# RelayExtension.net
KiCad netlist of a schematic drawn in Altium Designer
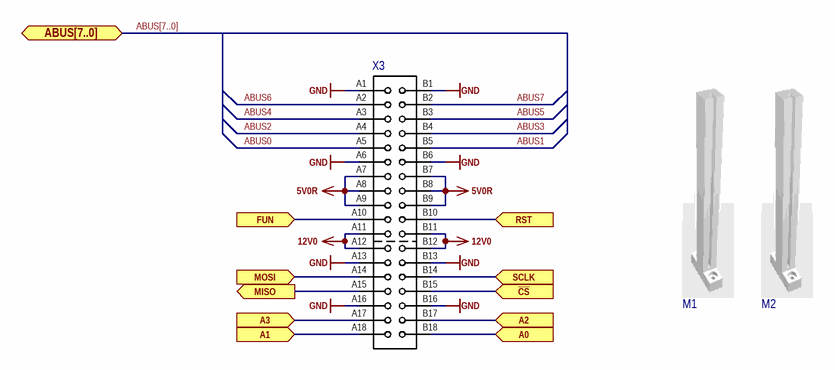
[diagram p0: RelayExtension.SchDoc]

(export (version "E")
  (design (tool "Eeschema 10.0.6"))
  (components
    (comp (ref "M1")
      (value "PCB Support")
      (footprint "PCB Tester Support")
      (fields
        (field (name "07. MANUFACTURER  PART NUMBER") "TBD")
        (field (name "13. CREATED DATE/NAME") "??? / Hören")
      )
      (libsource (lib "PCB-Tester-Board-V1") (part "PCB Tester Support"))
    )
    (comp (ref "M2")
      (value "PCB Support")
      (footprint "PCB Tester Support")
      (fields
        (field (name "07. MANUFACTURER  PART NUMBER") "TBD")
        (field (name "13. CREATED DATE/NAME") "??? / Hören")
      )
      (libsource (lib "PCB-Tester-Board-V1") (part "PCB Tester Support"))
    )
    (comp (ref "X3")
      (value "X")
      (footprint "PCIE-036-02-F-D-TH")
      (description "CONN PCI EXP FMALE 36POS 0.039")
      (fields
        (field (name "02. DISTRIBUTOR PART NUMBER") "SAM10625-ND")
        (field (name "07. MANUFACTURER  PART NUMBER") "PCIE-036-02-F-D-TH")
        (field (name "13. CREATED DATE/NAME") "??? / Hören")
      )
      (libsource (lib "Connectors") (part "PCIE-036-02-F-D-TH"))
    )
  )
  (nets
    (net (code "1") (name "/A0") (class "Default")
      (node (ref "X3") (pin "B18") (pinfunction "B18_B18") (pintype "passive"))
    )
    (net (code "2") (name "/A1") (class "Default")
      (node (ref "X3") (pin "A18") (pinfunction "A18_A18") (pintype "passive"))
    )
    (net (code "3") (name "/A2") (class "Default")
      (node (ref "X3") (pin "B17") (pinfunction "B17_B17") (pintype "passive"))
    )
    (net (code "4") (name "/A3") (class "Default")
      (node (ref "X3") (pin "A17") (pinfunction "A17_A17") (pintype "passive"))
    )
    (net (code "5") (name "/ABUS0") (class "Default")
      (node (ref "X3") (pin "A5") (pinfunction "A5_A5") (pintype "passive"))
    )
    (net (code "6") (name "/ABUS1") (class "Default")
      (node (ref "X3") (pin "B5") (pinfunction "B5_B5") (pintype "passive"))
    )
    (net (code "7") (name "/ABUS2") (class "Default")
      (node (ref "X3") (pin "A4") (pinfunction "A4_A4") (pintype "passive"))
    )
    (net (code "8") (name "/ABUS3") (class "Default")
      (node (ref "X3") (pin "B4") (pinfunction "B4_B4") (pintype "passive"))
    )
    (net (code "9") (name "/ABUS4") (class "Default")
      (node (ref "X3") (pin "A3") (pinfunction "A3_A3") (pintype "passive"))
    )
    (net (code "10") (name "/ABUS5") (class "Default")
      (node (ref "X3") (pin "B3") (pinfunction "B3_B3") (pintype "passive"))
    )
    (net (code "11") (name "/ABUS6") (class "Default")
      (node (ref "X3") (pin "A2") (pinfunction "A2_A2") (pintype "passive"))
    )
    (net (code "12") (name "/ABUS7") (class "Default")
      (node (ref "X3") (pin "B2") (pinfunction "B2_B2") (pintype "passive"))
    )
    (net (code "14") (name "/CS") (class "Default")
      (node (ref "X3") (pin "B15") (pinfunction "B15_B15") (pintype "passive"))
    )
    (net (code "15") (name "/FUN") (class "Default")
      (node (ref "X3") (pin "A10") (pinfunction "A10_A10") (pintype "passive"))
    )
    (net (code "16") (name "/MISO") (class "Default")
      (node (ref "X3") (pin "A15") (pinfunction "A15_A15") (pintype "passive"))
    )
    (net (code "17") (name "/MOSI") (class "Default")
      (node (ref "X3") (pin "A14") (pinfunction "A14_A14") (pintype "passive"))
    )
    (net (code "18") (name "/RST") (class "Default")
      (node (ref "X3") (pin "B10") (pinfunction "B10_B10") (pintype "passive"))
    )
    (net (code "19") (name "/SCLK") (class "Default")
      (node (ref "X3") (pin "B14") (pinfunction "B14_B14") (pintype "passive"))
    )
    (net (code "20") (name "5V0R") (class "Default")
      (node (ref "X3") (pin "A7") (pinfunction "A7_A7") (pintype "passive"))
      (node (ref "X3") (pin "A8") (pinfunction "A8_A8") (pintype "passive"))
      (node (ref "X3") (pin "A9") (pinfunction "A9_A9") (pintype "passive"))
      (node (ref "X3") (pin "B7") (pinfunction "B7_B7") (pintype "passive"))
      (node (ref "X3") (pin "B8") (pinfunction "B8_B8") (pintype "passive"))
      (node (ref "X3") (pin "B9") (pinfunction "B9_B9") (pintype "passive"))
    )
    (net (code "21") (name "12V0") (class "Default")
      (node (ref "X3") (pin "A11") (pinfunction "A11_A11") (pintype "passive"))
      (node (ref "X3") (pin "A12") (pinfunction "A12_A12") (pintype "passive"))
      (node (ref "X3") (pin "B11") (pinfunction "B11_B11") (pintype "passive"))
      (node (ref "X3") (pin "B12") (pinfunction "B12_B12") (pintype "passive"))
    )
    (net (code "22") (name "GND") (class "Default")
      (node (ref "X3") (pin "A1") (pinfunction "A1_A1") (pintype "passive"))
      (node (ref "X3") (pin "A13") (pinfunction "A13_A13") (pintype "passive"))
      (node (ref "X3") (pin "A16") (pinfunction "A16_A16") (pintype "passive"))
      (node (ref "X3") (pin "A6") (pinfunction "A6_A6") (pintype "passive"))
      (node (ref "X3") (pin "B1") (pinfunction "B1_B1") (pintype "passive"))
      (node (ref "X3") (pin "B13") (pinfunction "B13_B13") (pintype "passive"))
      (node (ref "X3") (pin "B16") (pinfunction "B16_B16") (pintype "passive"))
      (node (ref "X3") (pin "B6") (pinfunction "B6_B6") (pintype "passive"))
    )
  )
)
